# ZIntermediar2023.net
KiCad netlist of a schematic drawn in EAGLE
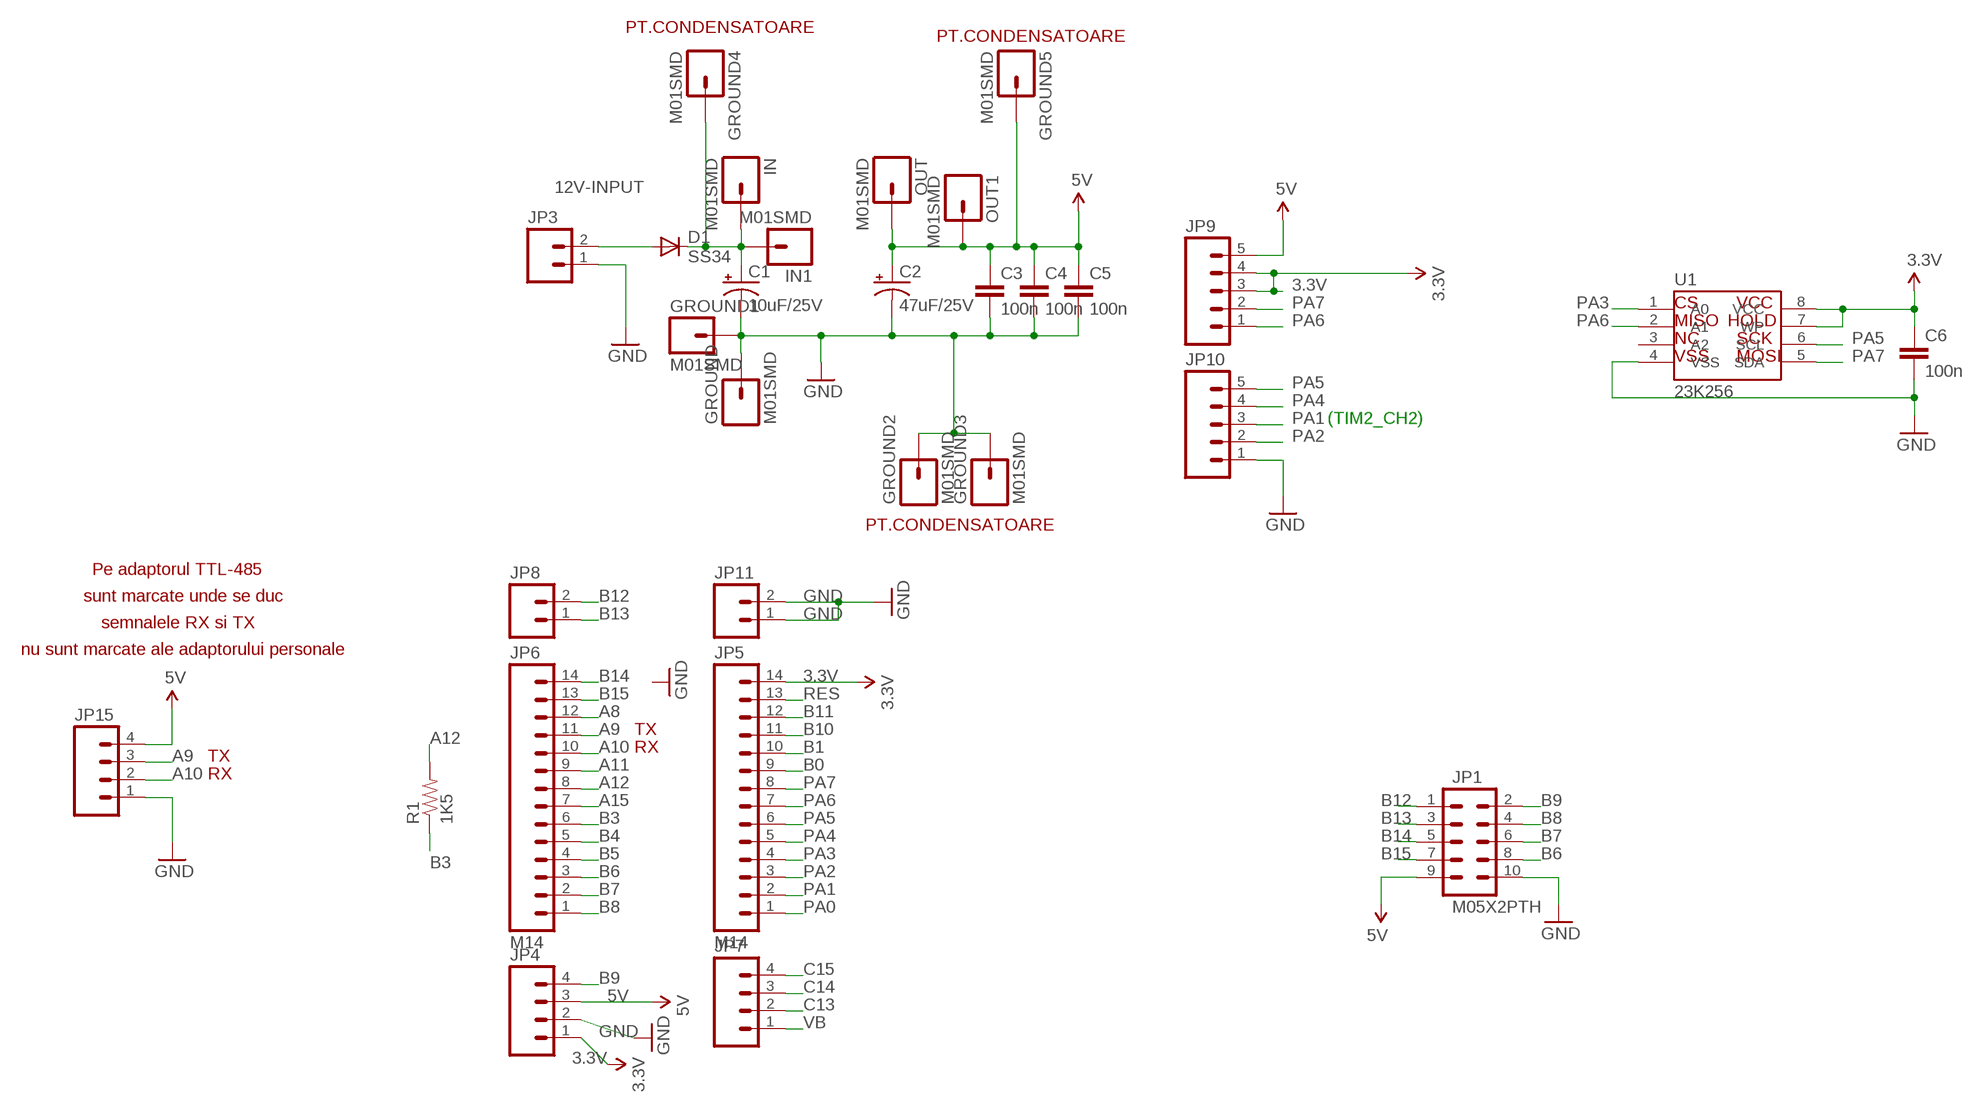
[diagram p0: schematic, sheet 1]

(export (version "E")
  (design (tool "Eeschema 10.0.6"))
  (components
    (comp (ref "C1")
      (value "10uF/25V")
      (footprint "eagle-import:PANASONIC_E")
      (libsource (lib "eagle-import") (part "CAP_POLE"))
    )
    (comp (ref "C2")
      (value "47uF/25V")
      (footprint "eagle-import:PANASONIC_E")
      (libsource (lib "eagle-import") (part "CAP_POLE"))
    )
    (comp (ref "C3")
      (value "100n")
      (footprint "eagle-import:1206")
      (libsource (lib "eagle-import") (part "CAP1206"))
    )
    (comp (ref "C4")
      (value "100n")
      (footprint "eagle-import:1206")
      (libsource (lib "eagle-import") (part "CAP1206"))
    )
    (comp (ref "C5")
      (value "100n")
      (footprint "eagle-import:1206")
      (libsource (lib "eagle-import") (part "CAP1206"))
    )
    (comp (ref "C6")
      (value "100n")
      (footprint "eagle-import:1206")
      (libsource (lib "eagle-import") (part "CAP1206"))
    )
    (comp (ref "D1")
      (value "SS34")
      (footprint "eagle-import:SMC")
      (libsource (lib "eagle-import") (part "DIODE-SMC"))
    )
    (comp (ref "GROUND")
      (value "M01SMD")
      (footprint "eagle-import:LUXEON-PAD")
      (libsource (lib "eagle-import") (part "M01SMD"))
    )
    (comp (ref "GROUND1")
      (value "M01SMD")
      (footprint "eagle-import:LUXEON-PAD")
      (libsource (lib "eagle-import") (part "M01SMD"))
    )
    (comp (ref "GROUND2")
      (value "M01SMD")
      (footprint "eagle-import:LUXEON-PAD")
      (libsource (lib "eagle-import") (part "M01SMD"))
    )
    (comp (ref "GROUND3")
      (value "M01SMD")
      (footprint "eagle-import:LUXEON-PAD")
      (libsource (lib "eagle-import") (part "M01SMD"))
    )
    (comp (ref "GROUND4")
      (value "M01SMD")
      (footprint "eagle-import:LUXEON-PAD")
      (libsource (lib "eagle-import") (part "M01SMD"))
    )
    (comp (ref "GROUND5")
      (value "M01SMD")
      (footprint "eagle-import:LUXEON-PAD")
      (libsource (lib "eagle-import") (part "M01SMD"))
    )
    (comp (ref "IN")
      (value "M01SMD")
      (footprint "eagle-import:LUXEON-PAD")
      (libsource (lib "eagle-import") (part "M01SMD"))
    )
    (comp (ref "IN1")
      (value "M01SMD")
      (footprint "eagle-import:LUXEON-PAD")
      (libsource (lib "eagle-import") (part "M01SMD"))
    )
    (comp (ref "JP1")
      (value "M05X2PTH")
      (footprint "eagle-import:AVR_ICSP")
      (libsource (lib "eagle-import") (part "M05X2PTH"))
    )
    (comp (ref "JP3")
      (value "M025MM")
      (footprint "eagle-import:SCREWTERMINAL-5MM-2")
      (libsource (lib "eagle-import") (part "M025MM"))
    )
    (comp (ref "JP4")
      (value "M04PTH")
      (footprint "eagle-import:1X04")
      (libsource (lib "eagle-import") (part "M04PTH"))
    )
    (comp (ref "JP5")
      (value "M14")
      (footprint "eagle-import:1X14")
      (libsource (lib "eagle-import") (part "M14"))
    )
    (comp (ref "JP6")
      (value "M14")
      (footprint "eagle-import:1X14")
      (libsource (lib "eagle-import") (part "M14"))
    )
    (comp (ref "JP7")
      (value "M04PTH")
      (footprint "eagle-import:1X04")
      (libsource (lib "eagle-import") (part "M04PTH"))
    )
    (comp (ref "JP8")
      (value "M02PTH")
      (footprint "eagle-import:1X02")
      (libsource (lib "eagle-import") (part "M02PTH"))
    )
    (comp (ref "JP9")
      (value "M05PTH_LONGPADS")
      (footprint "eagle-import:1X05_LONGPADS")
      (libsource (lib "eagle-import") (part "M05PTH_LONGPADS"))
    )
    (comp (ref "JP10")
      (value "M05PTH_LONGPADS")
      (footprint "eagle-import:1X05_LONGPADS")
      (libsource (lib "eagle-import") (part "M05PTH_LONGPADS"))
    )
    (comp (ref "JP11")
      (value "M02PTH")
      (footprint "eagle-import:1X02")
      (libsource (lib "eagle-import") (part "M02PTH"))
    )
    (comp (ref "JP15")
      (value "M04LONGPADS")
      (footprint "eagle-import:1X04_LONGPADS")
      (libsource (lib "eagle-import") (part "M04LONGPADS"))
    )
    (comp (ref "OUT")
      (value "M01SMD")
      (footprint "eagle-import:LUXEON-PAD")
      (libsource (lib "eagle-import") (part "M01SMD"))
    )
    (comp (ref "OUT1")
      (value "M01SMD")
      (footprint "eagle-import:LUXEON-PAD")
      (libsource (lib "eagle-import") (part "M01SMD"))
    )
    (comp (ref "R1")
      (value "1K5")
      (footprint "eagle-import:1206")
      (libsource (lib "eagle-import") (part "RESISTOR1206"))
    )
    (comp (ref "U1")
      (value "23K256")
      (footprint "eagle-import:SO08")
      (libsource (lib "eagle-import") (part "EEPROM-I2CSMD"))
    )
  )
  (nets
    (net (code "1") (name "/12V-INPUT") (class "Default")
      (node (ref "C1") (pin "+") (pinfunction "+_+") (pintype "passive"))
      (node (ref "D1") (pin "C") (pinfunction "C_C") (pintype "passive"))
      (node (ref "GROUND4") (pin "P$1") (pinfunction "1_P$1") (pintype "passive"))
      (node (ref "IN") (pin "P$1") (pinfunction "1_P$1") (pintype "passive"))
      (node (ref "IN1") (pin "P$1") (pinfunction "1_P$1") (pintype "passive"))
    )
    (net (code "2") (name "/A8") (class "Default")
      (node (ref "JP6") (pin "12") (pinfunction "12_12") (pintype "passive"))
    )
    (net (code "3") (name "/A9") (class "Default")
      (node (ref "JP15") (pin "3") (pinfunction "3_3") (pintype "passive"))
      (node (ref "JP6") (pin "11") (pinfunction "11_11") (pintype "passive"))
    )
    (net (code "4") (name "/A10") (class "Default")
      (node (ref "JP15") (pin "2") (pinfunction "2_2") (pintype "passive"))
      (node (ref "JP6") (pin "10") (pinfunction "10_10") (pintype "passive"))
    )
    (net (code "5") (name "/A11") (class "Default")
      (node (ref "JP6") (pin "9") (pinfunction "9_9") (pintype "passive"))
    )
    (net (code "6") (name "/A12") (class "Default")
      (node (ref "JP6") (pin "8") (pinfunction "8_8") (pintype "passive"))
      (node (ref "R1") (pin "2") (pinfunction "2_2") (pintype "passive"))
    )
    (net (code "7") (name "/A15") (class "Default")
      (node (ref "JP6") (pin "7") (pinfunction "7_7") (pintype "passive"))
    )
    (net (code "8") (name "/B0") (class "Default")
      (node (ref "JP5") (pin "9") (pinfunction "9_9") (pintype "passive"))
    )
    (net (code "9") (name "/B1") (class "Default")
      (node (ref "JP5") (pin "10") (pinfunction "10_10") (pintype "passive"))
    )
    (net (code "10") (name "/B3") (class "Default")
      (node (ref "JP6") (pin "6") (pinfunction "6_6") (pintype "passive"))
      (node (ref "R1") (pin "1") (pinfunction "1_1") (pintype "passive"))
    )
    (net (code "11") (name "/B4") (class "Default")
      (node (ref "JP6") (pin "5") (pinfunction "5_5") (pintype "passive"))
    )
    (net (code "12") (name "/B5") (class "Default")
      (node (ref "JP6") (pin "4") (pinfunction "4_4") (pintype "passive"))
    )
    (net (code "13") (name "/B6") (class "Default")
      (node (ref "JP1") (pin "8") (pinfunction "8_8") (pintype "passive"))
      (node (ref "JP6") (pin "3") (pinfunction "3_3") (pintype "passive"))
    )
    (net (code "14") (name "/B7") (class "Default")
      (node (ref "JP1") (pin "6") (pinfunction "6_6") (pintype "passive"))
      (node (ref "JP6") (pin "2") (pinfunction "2_2") (pintype "passive"))
    )
    (net (code "15") (name "/B8") (class "Default")
      (node (ref "JP1") (pin "4") (pinfunction "4_4") (pintype "passive"))
      (node (ref "JP6") (pin "1") (pinfunction "1_1") (pintype "passive"))
    )
    (net (code "16") (name "/B9") (class "Default")
      (node (ref "JP1") (pin "2") (pinfunction "2_2") (pintype "passive"))
      (node (ref "JP4") (pin "4") (pinfunction "4_4") (pintype "passive"))
    )
    (net (code "17") (name "/B10") (class "Default")
      (node (ref "JP5") (pin "11") (pinfunction "11_11") (pintype "passive"))
    )
    (net (code "18") (name "/B11") (class "Default")
      (node (ref "JP5") (pin "12") (pinfunction "12_12") (pintype "passive"))
    )
    (net (code "19") (name "/B12") (class "Default")
      (node (ref "JP1") (pin "1") (pinfunction "1_1") (pintype "passive"))
      (node (ref "JP8") (pin "2") (pinfunction "2_2") (pintype "passive"))
    )
    (net (code "20") (name "/B13") (class "Default")
      (node (ref "JP1") (pin "3") (pinfunction "3_3") (pintype "passive"))
      (node (ref "JP8") (pin "1") (pinfunction "1_1") (pintype "passive"))
    )
    (net (code "21") (name "/B14") (class "Default")
      (node (ref "JP1") (pin "5") (pinfunction "5_5") (pintype "passive"))
      (node (ref "JP6") (pin "14") (pinfunction "14_14") (pintype "passive"))
    )
    (net (code "22") (name "/B15") (class "Default")
      (node (ref "JP1") (pin "7") (pinfunction "7_7") (pintype "passive"))
      (node (ref "JP6") (pin "13") (pinfunction "13_13") (pintype "passive"))
    )
    (net (code "23") (name "/C13") (class "Default")
      (node (ref "JP7") (pin "2") (pinfunction "2_2") (pintype "passive"))
    )
    (net (code "24") (name "/C14") (class "Default")
      (node (ref "JP7") (pin "3") (pinfunction "3_3") (pintype "passive"))
    )
    (net (code "25") (name "/C15") (class "Default")
      (node (ref "JP7") (pin "4") (pinfunction "4_4") (pintype "passive"))
    )
    (net (code "26") (name "/PA0") (class "Default")
      (node (ref "JP5") (pin "1") (pinfunction "1_1") (pintype "passive"))
    )
    (net (code "27") (name "/PA1") (class "Default")
      (node (ref "JP10") (pin "3") (pinfunction "3_3") (pintype "passive"))
      (node (ref "JP5") (pin "2") (pinfunction "2_2") (pintype "passive"))
    )
    (net (code "28") (name "/PA2") (class "Default")
      (node (ref "JP10") (pin "2") (pinfunction "2_2") (pintype "passive"))
      (node (ref "JP5") (pin "3") (pinfunction "3_3") (pintype "passive"))
    )
    (net (code "29") (name "/PA3") (class "Default")
      (node (ref "JP5") (pin "4") (pinfunction "4_4") (pintype "passive"))
      (node (ref "U1") (pin "1") (pinfunction "A0_1") (pintype "bidirectional"))
    )
    (net (code "30") (name "/PA4") (class "Default")
      (node (ref "JP10") (pin "4") (pinfunction "4_4") (pintype "passive"))
      (node (ref "JP5") (pin "5") (pinfunction "5_5") (pintype "passive"))
    )
    (net (code "31") (name "/PA5") (class "Default")
      (node (ref "JP10") (pin "5") (pinfunction "5_5") (pintype "passive"))
      (node (ref "JP5") (pin "6") (pinfunction "6_6") (pintype "passive"))
      (node (ref "U1") (pin "6") (pinfunction "SCL_6") (pintype "bidirectional"))
    )
    (net (code "32") (name "/PA6") (class "Default")
      (node (ref "JP5") (pin "7") (pinfunction "7_7") (pintype "passive"))
      (node (ref "JP9") (pin "1") (pinfunction "1_1") (pintype "passive"))
      (node (ref "U1") (pin "2") (pinfunction "A1_2") (pintype "bidirectional"))
    )
    (net (code "33") (name "/PA7") (class "Default")
      (node (ref "JP5") (pin "8") (pinfunction "8_8") (pintype "passive"))
      (node (ref "JP9") (pin "2") (pinfunction "2_2") (pintype "passive"))
      (node (ref "U1") (pin "5") (pinfunction "SDA_5") (pintype "bidirectional"))
    )
    (net (code "34") (name "/RES") (class "Default")
      (node (ref "JP5") (pin "13") (pinfunction "13_13") (pintype "passive"))
    )
    (net (code "35") (name "/VB") (class "Default")
      (node (ref "JP7") (pin "1") (pinfunction "1_1") (pintype "passive"))
    )
    (net (code "36") (name "3.3V") (class "Default")
      (node (ref "C6") (pin "1") (pinfunction "1_1") (pintype "passive"))
      (node (ref "JP4") (pin "1") (pinfunction "1_1") (pintype "passive"))
      (node (ref "JP5") (pin "14") (pinfunction "14_14") (pintype "passive"))
      (node (ref "JP9") (pin "3") (pinfunction "3_3") (pintype "passive"))
      (node (ref "JP9") (pin "4") (pinfunction "4_4") (pintype "passive"))
      (node (ref "U1") (pin "7") (pinfunction "WP_7") (pintype "bidirectional"))
      (node (ref "U1") (pin "8") (pinfunction "VCC_8") (pintype "power_in"))
    )
    (net (code "37") (name "5V") (class "Default")
      (node (ref "C2") (pin "+") (pinfunction "+_+") (pintype "passive"))
      (node (ref "C3") (pin "1") (pinfunction "1_1") (pintype "passive"))
      (node (ref "C4") (pin "1") (pinfunction "1_1") (pintype "passive"))
      (node (ref "C5") (pin "1") (pinfunction "1_1") (pintype "passive"))
      (node (ref "GROUND5") (pin "P$1") (pinfunction "1_P$1") (pintype "passive"))
      (node (ref "JP1") (pin "9") (pinfunction "9_9") (pintype "passive"))
      (node (ref "JP15") (pin "4") (pinfunction "4_4") (pintype "passive"))
      (node (ref "JP4") (pin "3") (pinfunction "3_3") (pintype "passive"))
      (node (ref "JP9") (pin "5") (pinfunction "5_5") (pintype "passive"))
      (node (ref "OUT") (pin "P$1") (pinfunction "1_P$1") (pintype "passive"))
      (node (ref "OUT1") (pin "P$1") (pinfunction "1_P$1") (pintype "passive"))
    )
    (net (code "38") (name "GND") (class "Default")
      (node (ref "C1") (pin "-") (pinfunction "-_-") (pintype "passive"))
      (node (ref "C2") (pin "-") (pinfunction "-_-") (pintype "passive"))
      (node (ref "C3") (pin "2") (pinfunction "2_2") (pintype "passive"))
      (node (ref "C4") (pin "2") (pinfunction "2_2") (pintype "passive"))
      (node (ref "C5") (pin "2") (pinfunction "2_2") (pintype "passive"))
      (node (ref "C6") (pin "2") (pinfunction "2_2") (pintype "passive"))
      (node (ref "GROUND") (pin "P$1") (pinfunction "1_P$1") (pintype "passive"))
      (node (ref "GROUND1") (pin "P$1") (pinfunction "1_P$1") (pintype "passive"))
      (node (ref "GROUND2") (pin "P$1") (pinfunction "1_P$1") (pintype "passive"))
      (node (ref "GROUND3") (pin "P$1") (pinfunction "1_P$1") (pintype "passive"))
      (node (ref "JP1") (pin "10") (pinfunction "10_10") (pintype "passive"))
      (node (ref "JP10") (pin "1") (pinfunction "1_1") (pintype "passive"))
      (node (ref "JP11") (pin "1") (pinfunction "1_1") (pintype "passive"))
      (node (ref "JP11") (pin "2") (pinfunction "2_2") (pintype "passive"))
      (node (ref "JP15") (pin "1") (pinfunction "1_1") (pintype "passive"))
      (node (ref "JP3") (pin "1") (pinfunction "1_1") (pintype "passive"))
      (node (ref "JP4") (pin "2") (pinfunction "2_2") (pintype "passive"))
      (node (ref "U1") (pin "4") (pinfunction "VSS_4") (pintype "power_in"))
    )
    (net (code "39") (name "Net-(D1-PadA)") (class "Default")
      (node (ref "D1") (pin "A") (pinfunction "A_A") (pintype "passive"))
      (node (ref "JP3") (pin "2") (pinfunction "2_2") (pintype "passive"))
    )
    (net (code "40") (name "unconnected-(U1-A2-Pad3)") (class "Default")
      (node (ref "U1") (pin "3") (pinfunction "A2_3") (pintype "bidirectional"))
    )
  )
)
